# GPS.net
KiCad netlist of a schematic drawn in Altium Designer
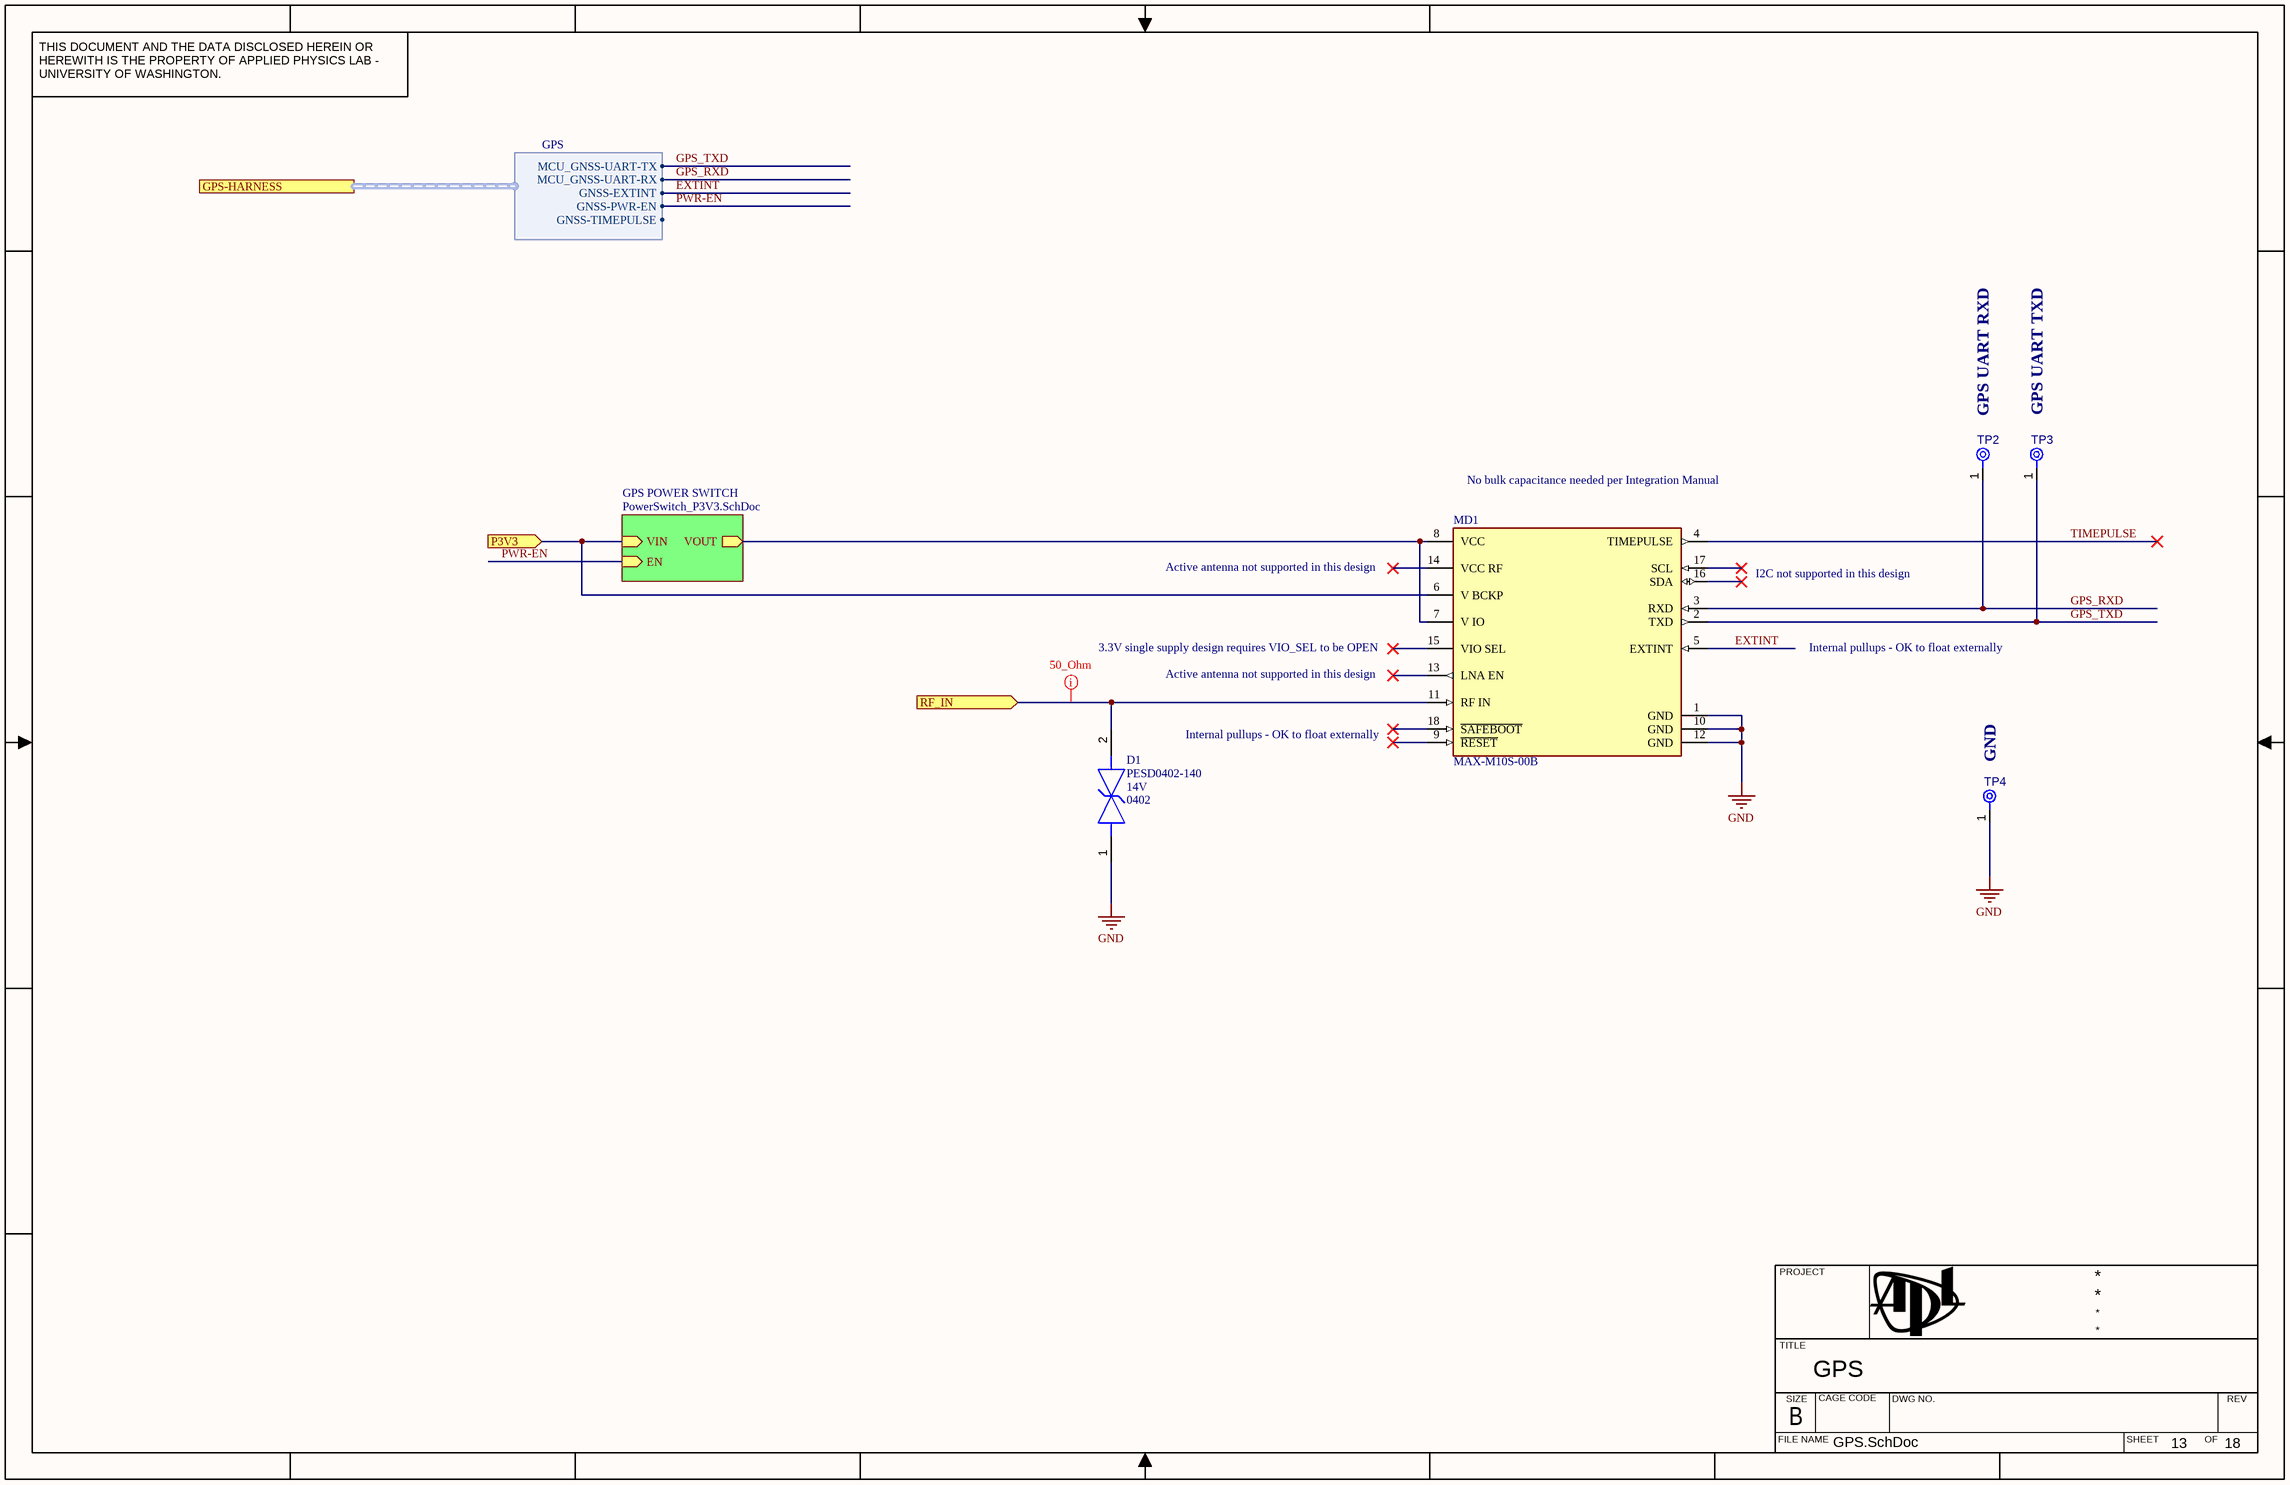
[diagram p0: GPS.SchDoc]

(export (version "E")
  (design (tool "Eeschema 10.0.6"))
  (components
    (comp (ref "D1")
      (value "PESD0402-140")
      (footprint "FP-PESD0402-MFG")
      (description "TVS DIODE 14VWM 40VC 0402")
      (fields (field (name "REVERSE STANDOFF VOLTAGE") "14V") (field (name "CASE/PACKAGE") "0402"))
      (libsource (lib "Applied Physics Lab") (part "edccc070dd5cba1f9372128faf3915e"))
    )
    (comp (ref "MD1")
      (value "MAX-M10S-00B")
      (footprint "FP-MAX-M10S-00B-MFG")
      (description "Gnss Lcc Rx, Rom, Tcxo, Lna, Saw")
      (libsource (lib "Applied Physics Lab") (part "a308a25f00fc71354910191737d199d"))
    )
    (comp (ref "TP2")
      (value "TPAD6R-CIRCLED")
      (footprint "TP06R - Circled")
      (description "0.6mm round with a silkscreen circle.")
      (libsource (lib "Applied Physics Lab") (part "CMP-001-0001-4"))
    )
    (comp (ref "TP3")
      (value "TPAD6R-CIRCLED")
      (footprint "TP06R - Circled")
      (description "0.6mm round with a silkscreen circle.")
      (libsource (lib "Applied Physics Lab") (part "CMP-001-0001-4"))
    )
    (comp (ref "TP4")
      (value "TPAD6R-CIRCLED")
      (footprint "TP06R - Circled")
      (description "0.6mm round with a silkscreen circle.")
      (libsource (lib "Applied Physics Lab") (part "CMP-001-0001-4"))
    )
  )
  (nets
    (net (code "2") (name "/EXTINT") (class "Default")
      (node (ref "MD1") (pin "5") (pinfunction "EXTINT_5") (pintype "input"))
    )
    (net (code "3") (name "/GPS_RXD") (class "Default")
      (node (ref "MD1") (pin "3") (pinfunction "RXD_3") (pintype "input"))
      (node (ref "TP2") (pin "1") (pinfunction "TP_1") (pintype "passive"))
    )
    (net (code "4") (name "/GPS_TXD") (class "Default")
      (node (ref "MD1") (pin "2") (pinfunction "TXD_2") (pintype "output"))
      (node (ref "TP3") (pin "1") (pinfunction "TP_1") (pintype "passive"))
    )
    (net (code "5") (name "/P3V3") (class "Default")
      (node (ref "MD1") (pin "6") (pinfunction "V_BCKP_6") (pintype "power_in"))
    )
    (net (code "7") (name "/RF_IN") (class "Default")
      (node (ref "D1") (pin "2") (pinfunction "2_2") (pintype "passive"))
      (node (ref "MD1") (pin "11") (pinfunction "RF_IN_11") (pintype "input"))
    )
    (net (code "8") (name "/TIMEPULSE") (class "Default")
      (node (ref "MD1") (pin "4") (pinfunction "TIMEPULSE_4") (pintype "output+no_connect"))
    )
    (net (code "9") (name "/VOUT") (class "Default")
      (node (ref "MD1") (pin "7") (pinfunction "V_IO_7") (pintype "power_in"))
      (node (ref "MD1") (pin "8") (pinfunction "VCC_8") (pintype "power_in"))
    )
    (net (code "11") (name "GND") (class "Default")
      (node (ref "D1") (pin "1") (pinfunction "1_1") (pintype "passive"))
      (node (ref "MD1") (pin "1") (pinfunction "GND_1") (pintype "power_in"))
      (node (ref "MD1") (pin "10") (pinfunction "GND_10") (pintype "power_in"))
      (node (ref "MD1") (pin "12") (pinfunction "GND_12") (pintype "power_in"))
      (node (ref "TP4") (pin "1") (pinfunction "TP_1") (pintype "passive"))
    )
    (net (code "12") (name "unconnected-(MD1-LNA_EN-Pad13)") (class "Default")
      (node (ref "MD1") (pin "13") (pinfunction "LNA_EN_13") (pintype "output+no_connect"))
    )
    (net (code "13") (name "unconnected-(MD1-SCL-Pad17)") (class "Default")
      (node (ref "MD1") (pin "17") (pinfunction "SCL_17") (pintype "input+no_connect"))
    )
    (net (code "14") (name "unconnected-(MD1-SDA-Pad16)") (class "Default")
      (node (ref "MD1") (pin "16") (pinfunction "SDA_16") (pintype "bidirectional+no_connect"))
    )
    (net (code "15") (name "unconnected-(MD1-VCC_RF-Pad14)") (class "Default")
      (node (ref "MD1") (pin "14") (pinfunction "VCC_RF_14") (pintype "power_in+no_connect"))
    )
    (net (code "16") (name "unconnected-(MD1-VIO_SEL-Pad15)") (class "Default")
      (node (ref "MD1") (pin "15") (pinfunction "VIO_SEL_15") (pintype "power_in+no_connect"))
    )
    (net (code "17") (name "unconnected-(MD1-~{RESET}-Pad9)") (class "Default")
      (node (ref "MD1") (pin "9") (pinfunction "~{RESET}_9") (pintype "input+no_connect"))
    )
    (net (code "18") (name "unconnected-(MD1-~{SAFEBOOT}-Pad18)") (class "Default")
      (node (ref "MD1") (pin "18") (pinfunction "~{SAFEBOOT}_18") (pintype "input+no_connect"))
    )
  )
)
